# SeriesParallel.net
KiCad netlist of a schematic drawn in Altium Designer
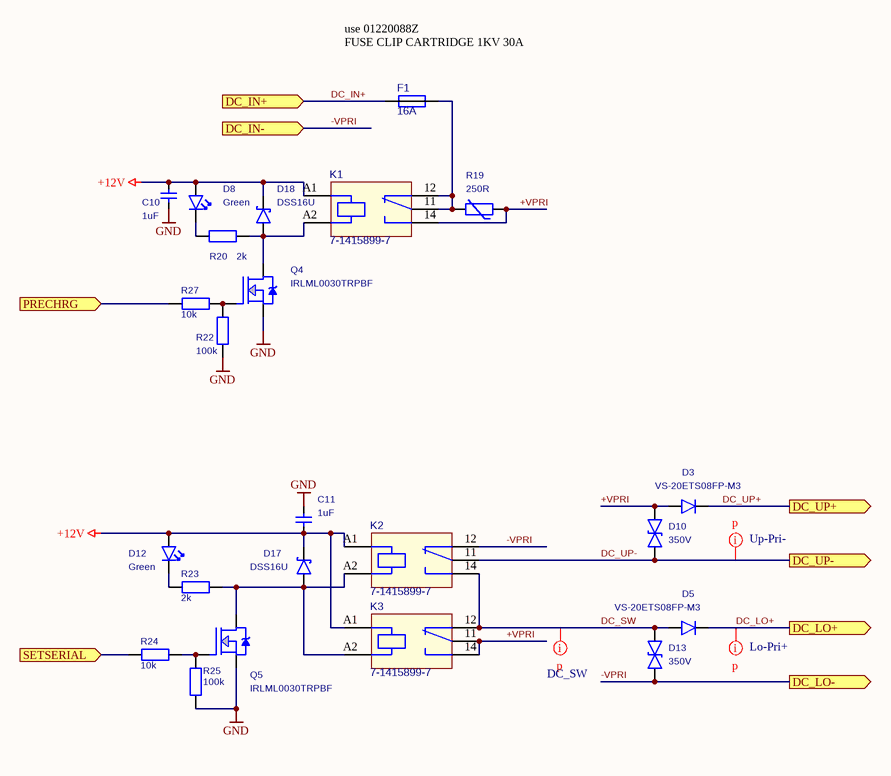
[diagram p0: SeriesParallel.SchDoc]

(export (version "E")
  (design (tool "Eeschema 10.0.6"))
  (components
    (comp (ref "C10")
      (value "1uF")
      (footprint "C-0805")
      (description "X7R 16V")
      (fields (field (name "MANUFACTURER") "Generic"))
      (libsource (lib "passive") (part "C"))
    )
    (comp (ref "C11")
      (value "1uF")
      (footprint "C-0805")
      (description "X7R 16V")
      (fields (field (name "MANUFACTURER") "Generic"))
      (libsource (lib "passive") (part "C"))
    )
    (comp (ref "D3")
      (value "VS-20ETS08FP-M3")
      (footprint "TO-220FP")
      (description "DIODE GEN PURP 800V 20A TO220FP")
      (fields (field (name "MANUFACTURER") "Vishay"))
      (libsource (lib "discret") (part "DIODE"))
    )
    (comp (ref "D5")
      (value "VS-20ETS08FP-M3")
      (footprint "TO-220FP")
      (description "DIODE GEN PURP 800V 20A TO220FP")
      (fields (field (name "MANUFACTURER") "Vishay"))
      (libsource (lib "discret") (part "DIODE"))
    )
    (comp (ref "D8")
      (value "Green")
      (footprint "LED-0603_GREEN")
      (description "LED GREEN CLEAR 0603 SMD")
      (fields
        (field (name "MANUFACTURER PART NUMBER") "150060GS75000")
        (field (name "MANUFACTURER") "Würth Elektronik")
      )
      (libsource (lib "discret") (part "DIOD LED"))
    )
    (comp (ref "D10")
      (value "350V")
      (footprint "DO-214AB(SMC)")
      (description "SIDACTOR 350V 3000A DO214AB")
      (fields
        (field (name "MANUFACTURER") "Littelfuse Inc.")
        (field (name "MANUFACTURER PART NUMBER") "P3800S3NLRP")
      )
      (libsource (lib "discret") (part "DIODE TVS Bi"))
    )
    (comp (ref "D12")
      (value "Green")
      (footprint "LED-0603_GREEN")
      (description "LED GREEN CLEAR 0603 SMD")
      (fields
        (field (name "MANUFACTURER PART NUMBER") "150060GS75000")
        (field (name "MANUFACTURER") "Würth Elektronik")
      )
      (libsource (lib "discret") (part "DIOD LED"))
    )
    (comp (ref "D13")
      (value "350V")
      (footprint "DO-214AB(SMC)")
      (description "SIDACTOR 350V 3000A DO214AB")
      (fields
        (field (name "MANUFACTURER") "Littelfuse Inc.")
        (field (name "MANUFACTURER PART NUMBER") "P3800S3NLRP")
      )
      (libsource (lib "discret") (part "DIODE TVS Bi"))
    )
    (comp (ref "D17")
      (value "DSS16U")
      (footprint "SOD-123")
      (description "SCHOTTKY 60V SOD-123FL")
      (fields (field (name "MANUFACTURER") "SMC Diode Solutions"))
      (libsource (lib "discret") (part "DIODE SHOTKI"))
    )
    (comp (ref "D18")
      (value "DSS16U")
      (footprint "SOD-123")
      (description "SCHOTTKY 60V SOD-123FL")
      (fields (field (name "MANUFACTURER") "SMC Diode Solutions"))
      (libsource (lib "discret") (part "DIODE SHOTKI"))
    )
    (comp (ref "F1")
      (value "16A")
      (footprint "FC-101-22")
      (description "FUSE 16A 600VDC")
      (fields
        (field (name "MANUFACTURER") "Littelfuse Inc.")
        (field (name "MANUFACTURER PART NUMBER") "0506016.MXP")
      )
      (libsource (lib "passive") (part "FUSE BRD"))
    )
    (comp (ref "K1")
      (value "7-1415899-7")
      (footprint "RT2")
      (description "RELAY SPDT 16A 12V")
      (fields (field (name "MANUFACTURER") "TE Connectivity"))
      (libsource (lib "Switches") (part "RZ"))
    )
    (comp (ref "K2")
      (value "7-1415899-7")
      (footprint "RT2")
      (description "RELAY SPDT 16A 12V")
      (fields (field (name "MANUFACTURER") "TE Connectivity"))
      (libsource (lib "Switches") (part "RZ"))
    )
    (comp (ref "K3")
      (value "7-1415899-7")
      (footprint "RT2")
      (description "RELAY SPDT 16A 12V")
      (fields (field (name "MANUFACTURER") "TE Connectivity"))
      (libsource (lib "Switches") (part "RZ"))
    )
    (comp (ref "Q4")
      (value "IRLML0030TRPBF")
      (footprint "SOT-23")
      (description "MOSFET N-CH 30V 5.3A SOT23")
      (fields (field (name "MANUFACTURER") "Infineon Technologies"))
      (libsource (lib "discret") (part "MOSF-N"))
    )
    (comp (ref "Q5")
      (value "IRLML0030TRPBF")
      (footprint "SOT-23")
      (description "MOSFET N-CH 30V 5.3A SOT23")
      (fields (field (name "MANUFACTURER") "Infineon Technologies"))
      (libsource (lib "discret") (part "MOSF-N"))
    )
    (comp (ref "R19")
      (value "250R")
      (footprint "PTCEL17")
      (description "PTC EL LDD 16D5 250R 860 135 B E")
      (fields
        (field (name "MANUFACTURER PART NUMBER") "PTCEL17R251SBE")
        (field (name "MANUFACTURER") "Vishay")
      )
      (libsource (lib "passive") (part "R_TERMO"))
    )
    (comp (ref "R20")
      (value "2k")
      (footprint "R-0603")
      (description "Resistor")
      (fields (field (name "MANUFACTURER") "Generic"))
      (libsource (lib "passive") (part "R"))
    )
    (comp (ref "R22")
      (value "100k")
      (footprint "R-0603")
      (description "Resistor")
      (fields (field (name "MANUFACTURER") "Generic"))
      (libsource (lib "passive") (part "R"))
    )
    (comp (ref "R23")
      (value "2k")
      (footprint "R-0603")
      (description "Resistor")
      (fields (field (name "MANUFACTURER") "Generic"))
      (libsource (lib "passive") (part "R"))
    )
    (comp (ref "R24")
      (value "10k")
      (footprint "R-0603")
      (description "Resistor")
      (fields (field (name "MANUFACTURER") "Generic"))
      (libsource (lib "passive") (part "R"))
    )
    (comp (ref "R25")
      (value "100k")
      (footprint "R-0603")
      (description "Resistor")
      (fields (field (name "MANUFACTURER") "Generic"))
      (libsource (lib "passive") (part "R"))
    )
    (comp (ref "R27")
      (value "10k")
      (footprint "R-0603")
      (description "Resistor")
      (fields (field (name "MANUFACTURER") "Generic"))
      (libsource (lib "passive") (part "R"))
    )
  )
  (nets
    (net (code "1") (name "+12V") (class "Default")
      (node (ref "C10") (pin "1") (pinfunction "1_1") (pintype "passive"))
      (node (ref "C11") (pin "1") (pinfunction "1_1") (pintype "passive"))
      (node (ref "D12") (pin "A") (pinfunction "A_A") (pintype "passive"))
      (node (ref "D17") (pin "K") (pinfunction "K_K") (pintype "passive"))
      (node (ref "D18") (pin "K") (pinfunction "K_K") (pintype "passive"))
      (node (ref "D8") (pin "A") (pinfunction "A_A") (pintype "passive"))
      (node (ref "K1") (pin "A1") (pintype "passive"))
      (node (ref "K2") (pin "A1") (pintype "passive"))
      (node (ref "K3") (pin "A1") (pintype "passive"))
    )
    (net (code "2") (name "/+VPRI") (class "Default")
      (node (ref "D10") (pin "K") (pinfunction "K_K") (pintype "passive"))
      (node (ref "D3") (pin "A") (pinfunction "A_A") (pintype "passive"))
      (node (ref "K1") (pin "14") (pintype "passive"))
      (node (ref "K3") (pin "11") (pintype "passive"))
      (node (ref "K3") (pin "14") (pintype "passive"))
      (node (ref "R19") (pin "1") (pinfunction "1_1") (pintype "passive"))
    )
    (net (code "3") (name "/-VPRI") (class "Default")
      (node (ref "D13") (pin "A") (pinfunction "A_A") (pintype "passive"))
      (node (ref "K2") (pin "12") (pintype "passive"))
    )
    (net (code "4") (name "/DC_IN+") (class "Default")
      (node (ref "F1") (pin "2") (pinfunction "2_2") (pintype "passive"))
    )
    (net (code "5") (name "/DC_LO+") (class "Default")
      (node (ref "D5") (pin "K") (pinfunction "K_K") (pintype "passive"))
    )
    (net (code "6") (name "/DC_SW") (class "Default")
      (node (ref "D13") (pin "K") (pinfunction "K_K") (pintype "passive"))
      (node (ref "D5") (pin "A") (pinfunction "A_A") (pintype "passive"))
      (node (ref "K2") (pin "14") (pintype "passive"))
      (node (ref "K3") (pin "12") (pintype "passive"))
    )
    (net (code "7") (name "/DC_UP+") (class "Default")
      (node (ref "D3") (pin "K") (pinfunction "K_K") (pintype "passive"))
    )
    (net (code "8") (name "/DC_UP-") (class "Default")
      (node (ref "D10") (pin "A") (pinfunction "A_A") (pintype "passive"))
      (node (ref "K2") (pin "11") (pintype "passive"))
    )
    (net (code "9") (name "/PRECHRG") (class "Default")
      (node (ref "R27") (pin "1") (pinfunction "1_1") (pintype "passive"))
    )
    (net (code "10") (name "/SETSERIAL") (class "Default")
      (node (ref "R24") (pin "1") (pinfunction "1_1") (pintype "passive"))
    )
    (net (code "11") (name "GND") (class "Default")
      (node (ref "C10") (pin "2") (pinfunction "2_2") (pintype "passive"))
      (node (ref "C11") (pin "2") (pinfunction "2_2") (pintype "passive"))
      (node (ref "Q4") (pin "2") (pinfunction "SOURCE_2") (pintype "passive"))
      (node (ref "Q5") (pin "2") (pinfunction "SOURCE_2") (pintype "passive"))
      (node (ref "R22") (pin "2") (pinfunction "2_2") (pintype "passive"))
      (node (ref "R25") (pin "1") (pinfunction "1_1") (pintype "passive"))
    )
    (net (code "12") (name "Net-(D8-PadK)") (class "Default")
      (node (ref "D8") (pin "K") (pinfunction "K_K") (pintype "passive"))
      (node (ref "R20") (pin "2") (pinfunction "2_2") (pintype "passive"))
    )
    (net (code "13") (name "Net-(D12-PadK)") (class "Default")
      (node (ref "D12") (pin "K") (pinfunction "K_K") (pintype "passive"))
      (node (ref "R23") (pin "2") (pinfunction "2_2") (pintype "passive"))
    )
    (net (code "14") (name "Net-(F1-Pad1)") (class "Default")
      (node (ref "F1") (pin "1") (pinfunction "1_1") (pintype "passive"))
      (node (ref "K1") (pin "11") (pintype "passive"))
      (node (ref "K1") (pin "12") (pintype "passive"))
      (node (ref "R19") (pin "2") (pinfunction "2_2") (pintype "passive"))
    )
    (net (code "15") (name "Net-(Q4-DRAIN)") (class "Default")
      (node (ref "D18") (pin "A") (pinfunction "A_A") (pintype "passive"))
      (node (ref "K1") (pin "A2") (pintype "passive"))
      (node (ref "Q4") (pin "3") (pinfunction "DRAIN_3") (pintype "passive"))
      (node (ref "R20") (pin "1") (pinfunction "1_1") (pintype "passive"))
    )
    (net (code "16") (name "Net-(Q4-GATE)") (class "Default")
      (node (ref "Q4") (pin "1") (pinfunction "GATE_1") (pintype "passive"))
      (node (ref "R22") (pin "1") (pinfunction "1_1") (pintype "passive"))
      (node (ref "R27") (pin "2") (pinfunction "2_2") (pintype "passive"))
    )
    (net (code "17") (name "Net-(Q5-DRAIN)") (class "Default")
      (node (ref "D17") (pin "A") (pinfunction "A_A") (pintype "passive"))
      (node (ref "K2") (pin "A2") (pintype "passive"))
      (node (ref "K3") (pin "A2") (pintype "passive"))
      (node (ref "Q5") (pin "3") (pinfunction "DRAIN_3") (pintype "passive"))
      (node (ref "R23") (pin "1") (pinfunction "1_1") (pintype "passive"))
    )
    (net (code "18") (name "Net-(Q5-GATE)") (class "Default")
      (node (ref "Q5") (pin "1") (pinfunction "GATE_1") (pintype "passive"))
      (node (ref "R24") (pin "2") (pinfunction "2_2") (pintype "passive"))
      (node (ref "R25") (pin "2") (pinfunction "2_2") (pintype "passive"))
    )
  )
)
